# PowerOut.net
KiCad netlist of a schematic drawn in Altium Designer
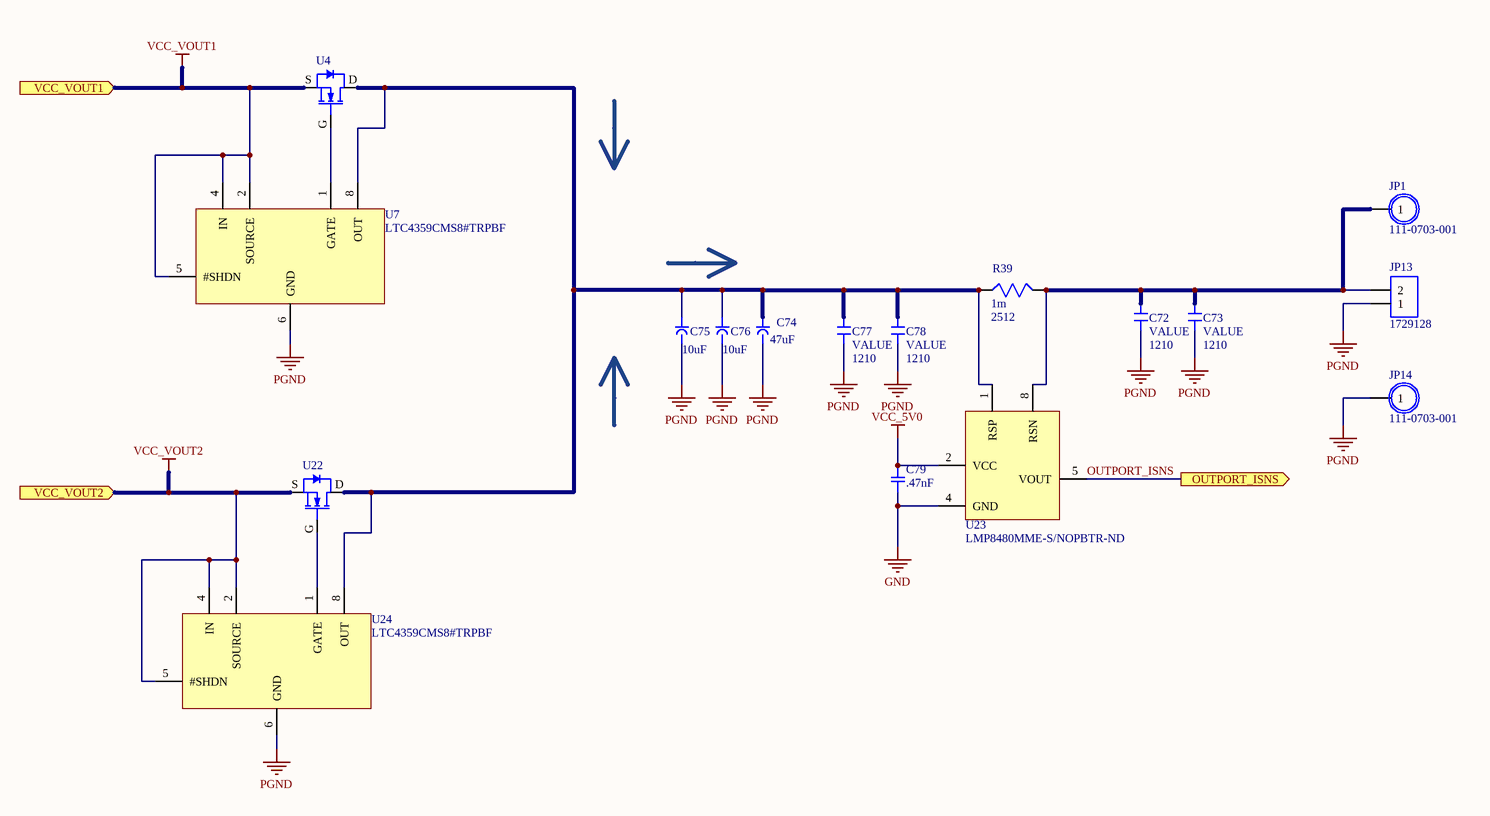
[diagram p0: PowerOut.SchDoc]

(export (version "E")
  (design (tool "Eeschema 10.0.6"))
  (components
    (comp (ref "C72")
      (value "VALUE")
      (footprint "1210 cap")
      (description "CAP SMD 1210")
      (fields (field (name "SIZE") "1210"))
      (libsource (lib "UniversalConverter_Symbols") (part "CAP SMD 1210"))
    )
    (comp (ref "C73")
      (value "VALUE")
      (footprint "1210 cap")
      (description "CAP SMD 1210")
      (fields (field (name "SIZE") "1210"))
      (libsource (lib "UniversalConverter_Symbols") (part "CAP SMD 1210"))
    )
    (comp (ref "C74")
      (value "10-EEE-FN1K470UVTR-ND")
      (footprint "EEE-FN1K470UV")
      (description "CAP ALUM 47UF 20% 80V SMD")
      (libsource (lib "UniversalConverter_Parts") (part "CAP ALUM 47UF"))
    )
    (comp (ref "C75")
      (value "10uF")
      (footprint "panasonic d8")
      (description "CAP ALUM 10UF 20% 80V SMD")
      (fields (field (name "Comment") "EEE-FN1K100XL"))
      (libsource (lib "UniversalConverter_Parts") (part "CAP ALUM 10UF"))
    )
    (comp (ref "C76")
      (value "10uF")
      (footprint "panasonic d8")
      (description "CAP ALUM 10UF 20% 80V SMD")
      (fields (field (name "Comment") "EEE-FN1K100XL"))
      (libsource (lib "UniversalConverter_Parts") (part "CAP ALUM 10UF"))
    )
    (comp (ref "C77")
      (value "VALUE")
      (footprint "1210 cap")
      (description "CAP SMD 1210")
      (fields (field (name "SIZE") "1210"))
      (libsource (lib "UniversalConverter_Symbols") (part "CAP SMD 1210"))
    )
    (comp (ref "C78")
      (value "VALUE")
      (footprint "1210 cap")
      (description "CAP SMD 1210")
      (fields (field (name "SIZE") "1210"))
      (libsource (lib "UniversalConverter_Symbols") (part "CAP SMD 1210"))
    )
    (comp (ref "C79")
      (value ".47nF")
      (footprint "SMD-0603C")
      (description "CAP CER 2200PF 50V X7R 0603")
      (fields
        (field (name "DIGI-KEY PART NUMBER") "490-5766-1-ND")
        (field (name "PART NUMBER") "GCJ188R71H222KA01D")
      )
      (libsource (lib "capacitor_murata_0603") (part "GCJ188R71H222KA01D"))
    )
    (comp (ref "JP1")
      (value "111-0703-001")
      (footprint "Banana Jack Post")
      (description "CONN BIND POST KNURLED BLACK‎")
      (libsource (lib "Personal_Library") (part "CONN BANANA JACK"))
    )
    (comp (ref "JP13")
      (value "1729128")
      (footprint "2x1_Term_Block")
      (description "Phoenix Contact-1729128")
      (libsource (lib "Personal_Library") (part "TERM BLK 2P SIDE ENT 5.08MM"))
    )
    (comp (ref "JP14")
      (value "111-0703-001")
      (footprint "Banana Jack Post")
      (description "CONN BIND POST KNURLED BLACK‎")
      (libsource (lib "Personal_Library") (part "CONN BANANA JACK"))
    )
    (comp (ref "R39")
      (value "1m")
      (footprint "2512")
      (description "RES SMD 2512 2W")
      (fields (field (name "SIZE") "2512"))
      (libsource (lib "UniversalConverter_Parts") (part "RES SMD 2512"))
    )
    (comp (ref "U4")
      (value "~")
      (footprint "PowerPAK® SO-8L SINGLE")
      (description "MOSFET N-CH 80V 60A PPAK SO-8")
      (libsource (lib "UniversalConverter_Parts") (part "FET SQJA80EP-T1_GE3"))
    )
    (comp (ref "U7")
      (value "LTC4359CMS8#TRPBF")
      (footprint "8-MSOP")
      (description "OR Controller N+1 ORing Controller N-Channel N:1 8-MSOP")
      (libsource (lib "UniversalConverter_Parts") (part "IC LTC4359"))
    )
    (comp (ref "U22")
      (value "~")
      (footprint "PowerPAK® SO-8L SINGLE")
      (description "MOSFET N-CH 80V 60A PPAK SO-8")
      (libsource (lib "UniversalConverter_Parts") (part "FET SQJA80EP-T1_GE3"))
    )
    (comp (ref "U23")
      (value "LMP8480MME-S/NOPBTR-ND")
      (footprint "DGK(S-PDSO-G8)")
      (description "IC CURR SENSE 1 CIRCUIT 8VSSOP")
      (libsource (lib "UniversalConverter_Parts") (part "IC LMP8480"))
    )
    (comp (ref "U24")
      (value "LTC4359CMS8#TRPBF")
      (footprint "8-MSOP")
      (description "OR Controller N+1 ORing Controller N-Channel N:1 8-MSOP")
      (libsource (lib "UniversalConverter_Parts") (part "IC LTC4359"))
    )
  )
  (nets
    (net (code "1") (name "/OUTPORT_ISNS") (class "Default")
      (node (ref "U23") (pin "5") (pinfunction "VOUT_5") (pintype "passive"))
    )
    (net (code "2") (name "GND") (class "Default")
      (node (ref "C79") (pin "2") (pinfunction "2_2") (pintype "passive"))
      (node (ref "U23") (pin "4") (pinfunction "GND_4") (pintype "passive"))
    )
    (net (code "3") (name "Net-(U4-GATE)") (class "Default")
      (node (ref "U4") (pin "G") (pinfunction "GATE_G") (pintype "passive"))
      (node (ref "U7") (pin "1") (pinfunction "GATE_1") (pintype "passive"))
    )
    (net (code "4") (name "Net-(U22-DRAIN)") (class "Default")
      (node (ref "C74") (pin "2") (pinfunction "2_2") (pintype "passive"))
      (node (ref "C75") (pin "1") (pinfunction "1_1") (pintype "passive"))
      (node (ref "C76") (pin "1") (pinfunction "1_1") (pintype "passive"))
      (node (ref "C77") (pin "1") (pinfunction "1_1") (pintype "passive"))
      (node (ref "C78") (pin "1") (pinfunction "1_1") (pintype "passive"))
      (node (ref "R39") (pin "1") (pinfunction "1_1") (pintype "passive"))
      (node (ref "U22") (pin "D") (pinfunction "DRAIN_D") (pintype "passive"))
      (node (ref "U23") (pin "1") (pinfunction "RSP_1") (pintype "passive"))
      (node (ref "U24") (pin "8") (pinfunction "OUT_8") (pintype "passive"))
      (node (ref "U4") (pin "D") (pinfunction "DRAIN_D") (pintype "passive"))
      (node (ref "U7") (pin "8") (pinfunction "OUT_8") (pintype "passive"))
    )
    (net (code "5") (name "Net-(U22-GATE)") (class "Default")
      (node (ref "U22") (pin "G") (pinfunction "GATE_G") (pintype "passive"))
      (node (ref "U24") (pin "1") (pinfunction "GATE_1") (pintype "passive"))
    )
    (net (code "6") (name "Net-(U23-RSN)") (class "Default")
      (node (ref "C72") (pin "1") (pinfunction "1_1") (pintype "passive"))
      (node (ref "C73") (pin "1") (pinfunction "1_1") (pintype "passive"))
      (node (ref "JP1") (pin "1") (pinfunction "1_1") (pintype "passive"))
      (node (ref "JP13") (pin "2") (pinfunction "2_2") (pintype "passive"))
      (node (ref "R39") (pin "2") (pinfunction "2_2") (pintype "passive"))
      (node (ref "U23") (pin "8") (pinfunction "RSN_8") (pintype "passive"))
    )
    (net (code "7") (name "PGND") (class "Default")
      (node (ref "C72") (pin "2") (pinfunction "2_2") (pintype "passive"))
      (node (ref "C73") (pin "2") (pinfunction "2_2") (pintype "passive"))
      (node (ref "C74") (pin "1") (pinfunction "1_1") (pintype "passive"))
      (node (ref "C75") (pin "2") (pinfunction "2_2") (pintype "passive"))
      (node (ref "C76") (pin "2") (pinfunction "2_2") (pintype "passive"))
      (node (ref "C77") (pin "2") (pinfunction "2_2") (pintype "passive"))
      (node (ref "C78") (pin "2") (pinfunction "2_2") (pintype "passive"))
      (node (ref "JP13") (pin "1") (pinfunction "1_1") (pintype "passive"))
      (node (ref "JP14") (pin "1") (pinfunction "1_1") (pintype "passive"))
      (node (ref "U24") (pin "6") (pinfunction "GND_6") (pintype "passive"))
      (node (ref "U7") (pin "6") (pinfunction "GND_6") (pintype "passive"))
    )
    (net (code "8") (name "VCC_5V0") (class "Default")
      (node (ref "C79") (pin "1") (pinfunction "1_1") (pintype "passive"))
      (node (ref "U23") (pin "2") (pinfunction "VCC_2") (pintype "passive"))
    )
    (net (code "9") (name "VCC_VOUT1") (class "Default")
      (node (ref "U4") (pin "S") (pinfunction "SOURCE_S") (pintype "passive"))
      (node (ref "U7") (pin "2") (pinfunction "SOURCE_2") (pintype "passive"))
      (node (ref "U7") (pin "4") (pinfunction "IN_4") (pintype "passive"))
      (node (ref "U7") (pin "5") (pinfunction "#SHDN_5") (pintype "passive"))
    )
    (net (code "10") (name "VCC_VOUT2") (class "Default")
      (node (ref "U22") (pin "S") (pinfunction "SOURCE_S") (pintype "passive"))
      (node (ref "U24") (pin "2") (pinfunction "SOURCE_2") (pintype "passive"))
      (node (ref "U24") (pin "4") (pinfunction "IN_4") (pintype "passive"))
      (node (ref "U24") (pin "5") (pinfunction "#SHDN_5") (pintype "passive"))
    )
  )
)
